# water.net
KiCad netlist of a schematic drawn in EAGLE
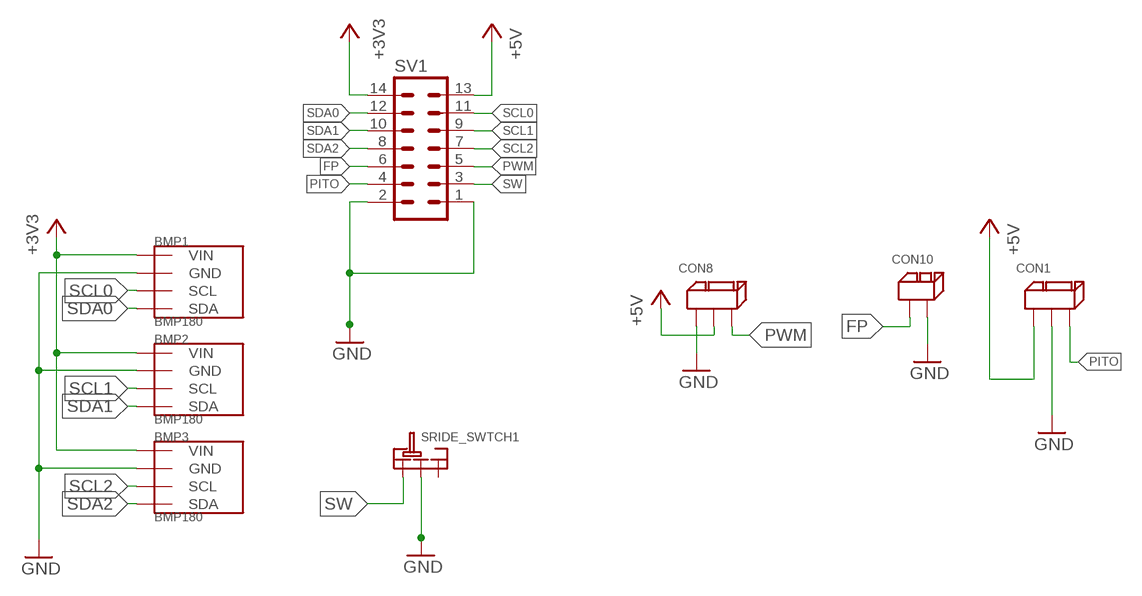
[diagram p0: schematic, sheet 1]

(export (version "E")
  (design (tool "Eeschema 10.0.6"))
  (components
    (comp (ref "BMP1")
      (value "BMP180")
      (footprint "eagle-import:GY-68")
      (libsource (lib "eagle-import") (part "BMP180"))
    )
    (comp (ref "BMP2")
      (value "BMP180")
      (footprint "eagle-import:GY-68")
      (libsource (lib "eagle-import") (part "BMP180"))
    )
    (comp (ref "BMP3")
      (value "BMP180")
      (footprint "eagle-import:GY-68")
      (libsource (lib "eagle-import") (part "BMP180"))
    )
    (comp (ref "CON1")
      (value "3PIN")
      (footprint "eagle-import:3PIN")
      (libsource (lib "eagle-import") (part "3PIN"))
    )
    (comp (ref "CON8")
      (value "3PIN")
      (footprint "eagle-import:3PIN")
      (libsource (lib "eagle-import") (part "3PIN"))
    )
    (comp (ref "CON10")
      (value "2PIN")
      (footprint "eagle-import:2PIN")
      (libsource (lib "eagle-import") (part "2PIN"))
    )
    (comp (ref "SRIDE_SWTCH1")
      (value "SRIDE_SWITCH")
      (footprint "eagle-import:SRIDE_SWITCH")
      (libsource (lib "eagle-import") (part "SRIDE_SWITCH"))
    )
    (comp (ref "SV1")
      (value "ML14L")
      (footprint "eagle-import:ML14L")
      (libsource (lib "eagle-import") (part "ML14L"))
    )
  )
  (nets
    (net (code "1") (name "+3V3") (class "Default")
      (node (ref "BMP1") (pin "P1") (pinfunction "VIN_P1") (pintype "bidirectional"))
      (node (ref "BMP2") (pin "P1") (pinfunction "VIN_P1") (pintype "bidirectional"))
      (node (ref "BMP3") (pin "P1") (pinfunction "VIN_P1") (pintype "bidirectional"))
      (node (ref "SV1") (pin "14") (pinfunction "14_14") (pintype "passive"))
    )
    (net (code "2") (name "+5V") (class "Default")
      (node (ref "CON1") (pin "P$1") (pinfunction "P$1_P$1") (pintype "bidirectional"))
      (node (ref "CON8") (pin "P$2") (pinfunction "P$2_P$2") (pintype "bidirectional"))
      (node (ref "SV1") (pin "13") (pinfunction "13_13") (pintype "passive"))
    )
    (net (code "3") (name "FP") (class "Default")
      (node (ref "CON10") (pin "P$1") (pinfunction "P$1_P$1") (pintype "bidirectional"))
      (node (ref "SV1") (pin "6") (pinfunction "6_6") (pintype "passive"))
    )
    (net (code "4") (name "GND") (class "Default")
      (node (ref "BMP1") (pin "P2") (pinfunction "GND_P2") (pintype "bidirectional"))
      (node (ref "BMP2") (pin "P2") (pinfunction "GND_P2") (pintype "bidirectional"))
      (node (ref "BMP3") (pin "P2") (pinfunction "GND_P2") (pintype "bidirectional"))
      (node (ref "CON1") (pin "P$2") (pinfunction "P$2_P$2") (pintype "bidirectional"))
      (node (ref "CON10") (pin "P$2") (pinfunction "P$2_P$2") (pintype "bidirectional"))
      (node (ref "CON8") (pin "P$1") (pinfunction "P$1_P$1") (pintype "bidirectional"))
      (node (ref "SRIDE_SWTCH1") (pin "LR") (pinfunction "LR_LR") (pintype "bidirectional"))
      (node (ref "SV1") (pin "1") (pinfunction "1_1") (pintype "passive"))
      (node (ref "SV1") (pin "2") (pinfunction "2_2") (pintype "passive"))
    )
    (net (code "5") (name "PITO") (class "Default")
      (node (ref "CON1") (pin "P$3") (pinfunction "P$3_P$3") (pintype "bidirectional"))
      (node (ref "SV1") (pin "4") (pinfunction "4_4") (pintype "passive"))
    )
    (net (code "6") (name "PWM") (class "Default")
      (node (ref "CON8") (pin "P$3") (pinfunction "P$3_P$3") (pintype "bidirectional"))
      (node (ref "SV1") (pin "5") (pinfunction "5_5") (pintype "passive"))
    )
    (net (code "7") (name "SCL0") (class "Default")
      (node (ref "BMP1") (pin "P3") (pinfunction "SCL_P3") (pintype "bidirectional"))
      (node (ref "SV1") (pin "11") (pinfunction "11_11") (pintype "passive"))
    )
    (net (code "8") (name "SCL1") (class "Default")
      (node (ref "BMP2") (pin "P3") (pinfunction "SCL_P3") (pintype "bidirectional"))
      (node (ref "SV1") (pin "9") (pinfunction "9_9") (pintype "passive"))
    )
    (net (code "9") (name "SCL2") (class "Default")
      (node (ref "BMP3") (pin "P3") (pinfunction "SCL_P3") (pintype "bidirectional"))
      (node (ref "SV1") (pin "7") (pinfunction "7_7") (pintype "passive"))
    )
    (net (code "10") (name "SDA0") (class "Default")
      (node (ref "BMP1") (pin "P4") (pinfunction "SDA_P4") (pintype "bidirectional"))
      (node (ref "SV1") (pin "12") (pinfunction "12_12") (pintype "passive"))
    )
    (net (code "11") (name "SDA1") (class "Default")
      (node (ref "BMP2") (pin "P4") (pinfunction "SDA_P4") (pintype "bidirectional"))
      (node (ref "SV1") (pin "10") (pinfunction "10_10") (pintype "passive"))
    )
    (net (code "12") (name "SDA2") (class "Default")
      (node (ref "BMP3") (pin "P4") (pinfunction "SDA_P4") (pintype "bidirectional"))
      (node (ref "SV1") (pin "8") (pinfunction "8_8") (pintype "passive"))
    )
    (net (code "13") (name "SW") (class "Default")
      (node (ref "SRIDE_SWTCH1") (pin "L") (pinfunction "L_L") (pintype "bidirectional"))
      (node (ref "SV1") (pin "3") (pinfunction "3_3") (pintype "passive"))
    )
    (net (code "14") (name "unconnected-(SRIDE_SWTCH1-PadR)") (class "Default")
      (node (ref "SRIDE_SWTCH1") (pin "R") (pinfunction "R_R") (pintype "bidirectional"))
    )
  )
)
